# to-pcbway.net
KiCad netlist of a schematic drawn in EAGLE
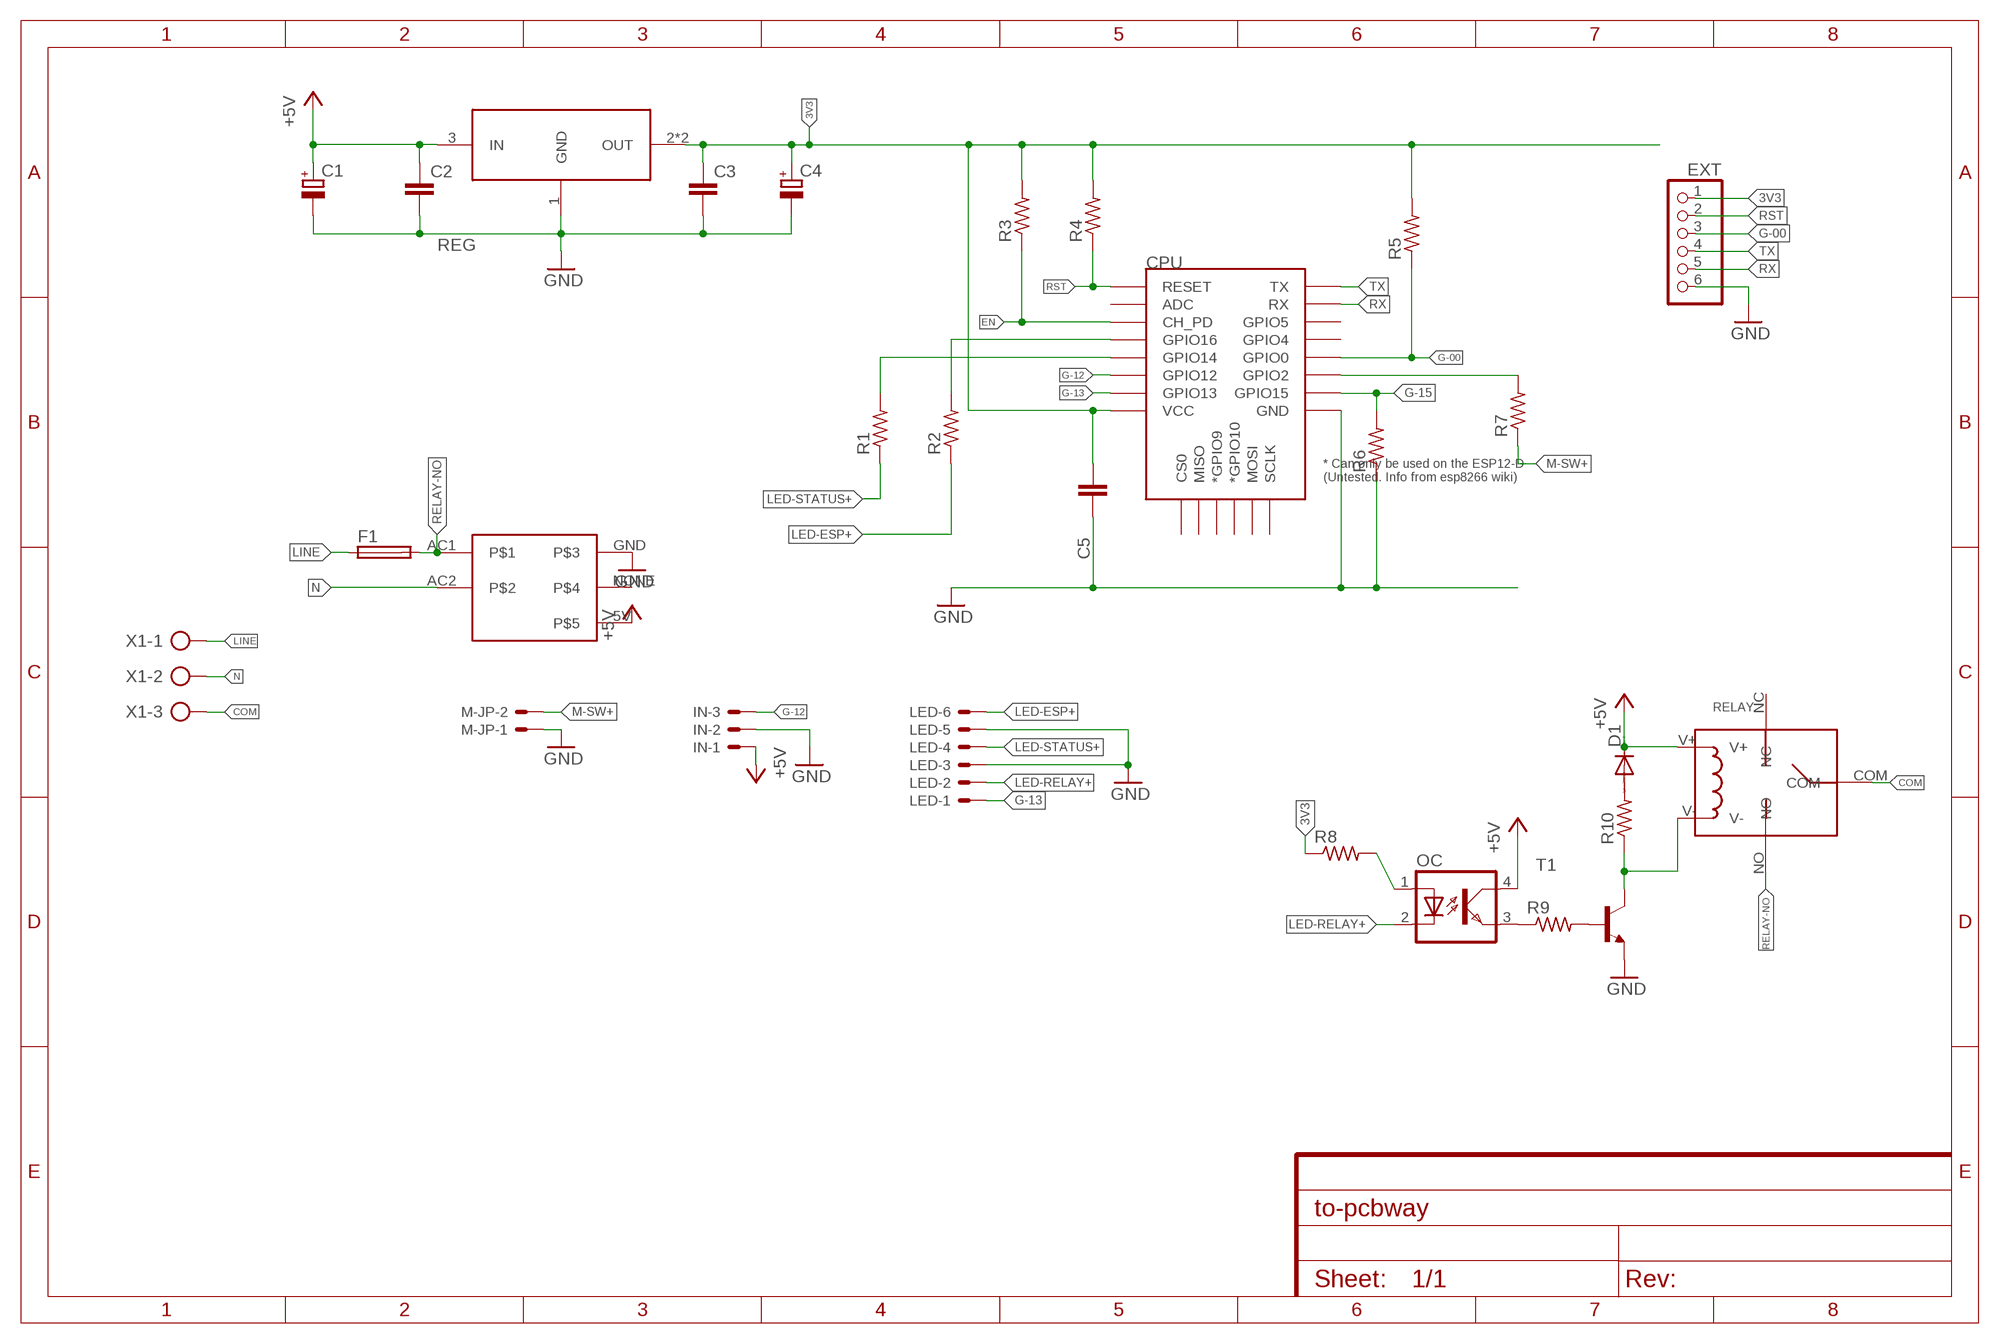
[diagram p0: schematic, sheet 1]

(export (version "E")
  (design (tool "Eeschema 10.0.6"))
  (components
    (comp (ref "C1")
      (value "CPOL-EUE2-5")
      (footprint "eagle-import:E2-5")
      (libsource (lib "eagle-import") (part "CPOL-EUE2-5"))
    )
    (comp (ref "C2")
      (value "C-EUC0603K")
      (footprint "eagle-import:C0603K")
      (libsource (lib "eagle-import") (part "C-EUC0603K"))
    )
    (comp (ref "C3")
      (value "C-EUC0603K")
      (footprint "eagle-import:C0603K")
      (libsource (lib "eagle-import") (part "C-EUC0603K"))
    )
    (comp (ref "C4")
      (value "CPOL-EUE2-5")
      (footprint "eagle-import:E2-5")
      (libsource (lib "eagle-import") (part "CPOL-EUE2-5"))
    )
    (comp (ref "C5")
      (value "C-EUC0805")
      (footprint "eagle-import:C0805")
      (libsource (lib "eagle-import") (part "C-EUC0805"))
    )
    (comp (ref "CPU")
      (value "ESP12ESMD")
      (footprint "eagle-import:ESP12E-SMD")
      (libsource (lib "eagle-import") (part "ESP12ESMD"))
    )
    (comp (ref "D1")
      (value "1N4148DO35-7")
      (footprint "eagle-import:DO35-7")
      (libsource (lib "eagle-import") (part "1N4148DO35-7"))
    )
    (comp (ref "EXT")
      (value "PINHD-1X6")
      (footprint "eagle-import:1X06")
      (libsource (lib "eagle-import") (part "PINHD-1X6"))
    )
    (comp (ref "F1")
      (value "FUSESH22,5")
      (footprint "eagle-import:SH22,5")
      (libsource (lib "eagle-import") (part "FUSESH22,5"))
    )
    (comp (ref "IN")
      (value "53048-03")
      (footprint "eagle-import:53048-03")
      (fields (field (name "MF") "WALDOM/MOLEX") (field (name "MPN") "53048-0310"))
      (libsource (lib "eagle-import") (part "53?-03048"))
    )
    (comp (ref "LED")
      (value "53048-06")
      (footprint "eagle-import:53048-06")
      (fields (field (name "MF") "WALDOM/MOLEX") (field (name "MPN") "53048-0610"))
      (libsource (lib "eagle-import") (part "53?-06048"))
    )
    (comp (ref "M-JP")
      (value "53048-02")
      (footprint "eagle-import:53048-02")
      (fields (field (name "MF") "MOLEX") (field (name "MPN") "53048-0210"))
      (libsource (lib "eagle-import") (part "53?-02048"))
    )
    (comp (ref "OC")
      (value "PC817")
      (footprint "eagle-import:DIL04")
      (fields (field (name "MPN") "PC817X4J000F"))
      (libsource (lib "eagle-import") (part "PC817"))
    )
    (comp (ref "R1")
      (value "R-US_R0603")
      (footprint "eagle-import:R0603")
      (libsource (lib "eagle-import") (part "R-US_R0603"))
    )
    (comp (ref "R2")
      (value "R-US_R0603")
      (footprint "eagle-import:R0603")
      (libsource (lib "eagle-import") (part "R-US_R0603"))
    )
    (comp (ref "R3")
      (value "R-US_R0603")
      (footprint "eagle-import:R0603")
      (libsource (lib "eagle-import") (part "R-US_R0603"))
    )
    (comp (ref "R4")
      (value "R-US_R0603")
      (footprint "eagle-import:R0603")
      (libsource (lib "eagle-import") (part "R-US_R0603"))
    )
    (comp (ref "R5")
      (value "R-US_R0603")
      (footprint "eagle-import:R0603")
      (libsource (lib "eagle-import") (part "R-US_R0603"))
    )
    (comp (ref "R6")
      (value "R-US_R0603")
      (footprint "eagle-import:R0603")
      (libsource (lib "eagle-import") (part "R-US_R0603"))
    )
    (comp (ref "R7")
      (value "R-US_R0603")
      (footprint "eagle-import:R0603")
      (libsource (lib "eagle-import") (part "R-US_R0603"))
    )
    (comp (ref "R8")
      (value "R-US_M0805")
      (footprint "eagle-import:M0805")
      (libsource (lib "eagle-import") (part "R-US_M0805"))
    )
    (comp (ref "R9")
      (value "R-US_M0805")
      (footprint "eagle-import:M0805")
      (libsource (lib "eagle-import") (part "R-US_M0805"))
    )
    (comp (ref "R10")
      (value "R-US_M0805")
      (footprint "eagle-import:M0805")
      (libsource (lib "eagle-import") (part "R-US_M0805"))
    )
    (comp (ref "REG")
      (value "AMS1117-3.3")
      (footprint "eagle-import:SOT-223")
      (libsource (lib "eagle-import") (part "AMS1117-3.3"))
    )
    (comp (ref "RELAY")
      (value "RELAY-SONGLE")
      (footprint "eagle-import:RELAY-SONGLE")
      (libsource (lib "eagle-import") (part "RELAY-SONGLE"))
    )
    (comp (ref "T1")
      (value "BC817-NPN-SOT23-BEC")
      (footprint "eagle-import:SOT23-BEC")
      (libsource (lib "eagle-import") (part "-NPN-SOT23-BECBC817"))
    )
    (comp (ref "U$4")
      (value "POWERSUPPLY-5V-700MA")
      (footprint "eagle-import:POWERSUPPLY-5V-700MA")
      (libsource (lib "eagle-import") (part "POWERSUPPLY-5V-700MA"))
    )
    (comp (ref "X1")
      (value "AK300/3")
      (footprint "eagle-import:AK300_3")
      (libsource (lib "eagle-import") (part "AK300/3"))
    )
  )
  (nets
    (net (code "1") (name "+5V") (class "Default")
      (node (ref "C1") (pin "+") (pinfunction "+_+") (pintype "passive"))
      (node (ref "C2") (pin "1") (pinfunction "1_1") (pintype "passive"))
      (node (ref "D1") (pin "C") (pinfunction "C_C") (pintype "passive"))
      (node (ref "IN") (pin "1") (pinfunction "S_1") (pintype "passive"))
      (node (ref "OC") (pin "4") (pinfunction "COL_4") (pintype "passive"))
      (node (ref "REG") (pin "3") (pinfunction "IN_3") (pintype "input"))
      (node (ref "RELAY") (pin "V+") (pinfunction "V+_V+") (pintype "bidirectional"))
      (node (ref "U$4") (pin "5V") (pinfunction "P$5_5V") (pintype "bidirectional"))
    )
    (net (code "2") (name "3V3") (class "Default")
      (node (ref "C3") (pin "1") (pinfunction "1_1") (pintype "passive"))
      (node (ref "C4") (pin "+") (pinfunction "+_+") (pintype "passive"))
      (node (ref "C5") (pin "1") (pinfunction "1_1") (pintype "passive"))
      (node (ref "CPU") (pin "VCC") (pinfunction "VCC_VCC") (pintype "bidirectional"))
      (node (ref "EXT") (pin "1") (pinfunction "1_1") (pintype "passive"))
      (node (ref "R3") (pin "2") (pinfunction "2_2") (pintype "passive"))
      (node (ref "R4") (pin "2") (pinfunction "2_2") (pintype "passive"))
      (node (ref "R5") (pin "2") (pinfunction "2_2") (pintype "passive"))
      (node (ref "R8") (pin "1") (pinfunction "1_1") (pintype "passive"))
      (node (ref "REG") (pin "2") (pinfunction "OUT_2") (pintype "output"))
      (node (ref "REG") (pin "4") (pinfunction "OUT_4") (pintype "output"))
    )
    (net (code "3") (name "COM") (class "Default")
      (node (ref "RELAY") (pin "COM") (pinfunction "COM_COM") (pintype "bidirectional"))
      (node (ref "X1") (pin "3") (pinfunction "KL_3") (pintype "passive"))
    )
    (net (code "4") (name "EN") (class "Default")
      (node (ref "CPU") (pin "CH_PD") (pinfunction "CH_PD_CH_PD") (pintype "bidirectional"))
      (node (ref "R3") (pin "1") (pinfunction "1_1") (pintype "passive"))
    )
    (net (code "5") (name "G-00") (class "Default")
      (node (ref "CPU") (pin "GPIO0") (pinfunction "GPIO0_GPIO0") (pintype "bidirectional"))
      (node (ref "EXT") (pin "3") (pinfunction "3_3") (pintype "passive"))
      (node (ref "R5") (pin "1") (pinfunction "1_1") (pintype "passive"))
    )
    (net (code "6") (name "G-12") (class "Default")
      (node (ref "CPU") (pin "GPIO12") (pinfunction "GPIO12_GPIO12") (pintype "bidirectional"))
      (node (ref "IN") (pin "3") (pinfunction "S_3") (pintype "passive"))
    )
    (net (code "7") (name "G-13") (class "Default")
      (node (ref "CPU") (pin "GPIO13") (pinfunction "GPIO13_GPIO13") (pintype "bidirectional"))
      (node (ref "LED") (pin "1") (pinfunction "S_1") (pintype "passive"))
    )
    (net (code "8") (name "G-15") (class "Default")
      (node (ref "CPU") (pin "GPIO15") (pinfunction "GPIO15_GPIO15") (pintype "bidirectional"))
      (node (ref "R6") (pin "2") (pinfunction "2_2") (pintype "passive"))
    )
    (net (code "9") (name "GND") (class "Default")
      (node (ref "C1") (pin "-") (pinfunction "-_-") (pintype "passive"))
      (node (ref "C2") (pin "2") (pinfunction "2_2") (pintype "passive"))
      (node (ref "C3") (pin "2") (pinfunction "2_2") (pintype "passive"))
      (node (ref "C4") (pin "-") (pinfunction "-_-") (pintype "passive"))
      (node (ref "C5") (pin "2") (pinfunction "2_2") (pintype "passive"))
      (node (ref "CPU") (pin "GND") (pinfunction "GND_GND") (pintype "bidirectional"))
      (node (ref "EXT") (pin "6") (pinfunction "6_6") (pintype "passive"))
      (node (ref "IN") (pin "2") (pinfunction "S_2") (pintype "passive"))
      (node (ref "LED") (pin "3") (pinfunction "S_3") (pintype "passive"))
      (node (ref "LED") (pin "5") (pinfunction "S_5") (pintype "passive"))
      (node (ref "M-JP") (pin "1") (pinfunction "S_1") (pintype "passive"))
      (node (ref "R6") (pin "1") (pinfunction "1_1") (pintype "passive"))
      (node (ref "REG") (pin "1") (pinfunction "GND_1") (pintype "passive"))
      (node (ref "T1") (pin "E") (pinfunction "E_E") (pintype "passive"))
      (node (ref "U$4") (pin "GND") (pinfunction "P$3_GND") (pintype "bidirectional"))
    )
    (net (code "10") (name "LED-ESP+") (class "Default")
      (node (ref "LED") (pin "6") (pinfunction "S_6") (pintype "passive"))
      (node (ref "R2") (pin "1") (pinfunction "1_1") (pintype "passive"))
    )
    (net (code "11") (name "LED-RELAY+") (class "Default")
      (node (ref "LED") (pin "2") (pinfunction "S_2") (pintype "passive"))
      (node (ref "OC") (pin "2") (pinfunction "C_2") (pintype "passive"))
    )
    (net (code "12") (name "LED-STATUS+") (class "Default")
      (node (ref "LED") (pin "4") (pinfunction "S_4") (pintype "passive"))
      (node (ref "R1") (pin "1") (pinfunction "1_1") (pintype "passive"))
    )
    (net (code "13") (name "LINE") (class "Default")
      (node (ref "F1") (pin "1") (pinfunction "1_1") (pintype "passive"))
      (node (ref "X1") (pin "1") (pinfunction "KL_1") (pintype "passive"))
    )
    (net (code "14") (name "M-SW+") (class "Default")
      (node (ref "M-JP") (pin "2") (pinfunction "S_2") (pintype "passive"))
      (node (ref "R7") (pin "1") (pinfunction "1_1") (pintype "passive"))
    )
    (net (code "15") (name "N") (class "Default")
      (node (ref "U$4") (pin "AC2") (pinfunction "P$2_AC2") (pintype "bidirectional"))
      (node (ref "X1") (pin "2") (pinfunction "KL_2") (pintype "passive"))
    )
    (net (code "16") (name "Net-(CPU-PadGPIO2)") (class "Default")
      (node (ref "CPU") (pin "GPIO2") (pinfunction "GPIO2_GPIO2") (pintype "bidirectional"))
      (node (ref "R7") (pin "2") (pinfunction "2_2") (pintype "passive"))
    )
    (net (code "17") (name "Net-(CPU-PadGPIO14)") (class "Default")
      (node (ref "CPU") (pin "GPIO14") (pinfunction "GPIO14_GPIO14") (pintype "bidirectional"))
      (node (ref "R1") (pin "2") (pinfunction "2_2") (pintype "passive"))
    )
    (net (code "18") (name "Net-(CPU-PadGPIO16)") (class "Default")
      (node (ref "CPU") (pin "GPIO16") (pinfunction "GPIO16_GPIO16") (pintype "bidirectional"))
      (node (ref "R2") (pin "2") (pinfunction "2_2") (pintype "passive"))
    )
    (net (code "19") (name "Net-(D1-PadA)") (class "Default")
      (node (ref "D1") (pin "A") (pinfunction "A_A") (pintype "passive"))
      (node (ref "R10") (pin "2") (pinfunction "2_2") (pintype "passive"))
    )
    (net (code "20") (name "Net-(OC-A)") (class "Default")
      (node (ref "OC") (pin "1") (pinfunction "A_1") (pintype "passive"))
      (node (ref "R8") (pin "2") (pinfunction "2_2") (pintype "passive"))
    )
    (net (code "21") (name "Net-(OC-EMIT)") (class "Default")
      (node (ref "OC") (pin "3") (pinfunction "EMIT_3") (pintype "passive"))
      (node (ref "R9") (pin "1") (pinfunction "1_1") (pintype "passive"))
    )
    (net (code "22") (name "Net-(R9-Pad2)") (class "Default")
      (node (ref "R9") (pin "2") (pinfunction "2_2") (pintype "passive"))
      (node (ref "T1") (pin "B") (pinfunction "B_B") (pintype "passive"))
    )
    (net (code "23") (name "Net-(R10-Pad1)") (class "Default")
      (node (ref "R10") (pin "1") (pinfunction "1_1") (pintype "passive"))
      (node (ref "RELAY") (pin "V-") (pinfunction "V-_V-") (pintype "bidirectional"))
      (node (ref "T1") (pin "C") (pinfunction "C_C") (pintype "passive"))
    )
    (net (code "24") (name "RELAY-NO") (class "Default")
      (node (ref "F1") (pin "2") (pinfunction "2_2") (pintype "passive"))
      (node (ref "RELAY") (pin "NO") (pinfunction "NO_NO") (pintype "bidirectional"))
      (node (ref "U$4") (pin "AC1") (pinfunction "P$1_AC1") (pintype "bidirectional"))
    )
    (net (code "25") (name "RST") (class "Default")
      (node (ref "CPU") (pin "RESET") (pinfunction "RESET_RESET") (pintype "bidirectional"))
      (node (ref "EXT") (pin "2") (pinfunction "2_2") (pintype "passive"))
      (node (ref "R4") (pin "1") (pinfunction "1_1") (pintype "passive"))
    )
    (net (code "26") (name "RX") (class "Default")
      (node (ref "CPU") (pin "RXD0") (pinfunction "RX_RXD0") (pintype "bidirectional"))
      (node (ref "EXT") (pin "5") (pinfunction "5_5") (pintype "passive"))
    )
    (net (code "27") (name "TX") (class "Default")
      (node (ref "CPU") (pin "TXD0") (pinfunction "TX_TXD0") (pintype "bidirectional"))
      (node (ref "EXT") (pin "4") (pinfunction "4_4") (pintype "passive"))
    )
    (net (code "28") (name "unconnected-(CPU-*GPIO9-PadGPIO9)") (class "Default")
      (node (ref "CPU") (pin "GPIO9") (pinfunction "*GPIO9_GPIO9") (pintype "bidirectional"))
    )
    (net (code "29") (name "unconnected-(CPU-*GPIO10-PadGPIO10)") (class "Default")
      (node (ref "CPU") (pin "GPIO10") (pinfunction "*GPIO10_GPIO10") (pintype "bidirectional"))
    )
    (net (code "30") (name "unconnected-(CPU-PadADC)") (class "Default")
      (node (ref "CPU") (pin "ADC") (pinfunction "ADC_ADC") (pintype "bidirectional"))
    )
    (net (code "31") (name "unconnected-(CPU-PadCS0)") (class "Default")
      (node (ref "CPU") (pin "CS0") (pinfunction "CS0_CS0") (pintype "bidirectional"))
    )
    (net (code "32") (name "unconnected-(CPU-PadGPIO4)") (class "Default")
      (node (ref "CPU") (pin "GPIO4") (pinfunction "GPIO4_GPIO4") (pintype "bidirectional"))
    )
    (net (code "33") (name "unconnected-(CPU-PadGPIO5)") (class "Default")
      (node (ref "CPU") (pin "GPIO5") (pinfunction "GPIO5_GPIO5") (pintype "bidirectional"))
    )
    (net (code "34") (name "unconnected-(CPU-PadMISO)") (class "Default")
      (node (ref "CPU") (pin "MISO") (pinfunction "MISO_MISO") (pintype "bidirectional"))
    )
    (net (code "35") (name "unconnected-(CPU-PadMOSI)") (class "Default")
      (node (ref "CPU") (pin "MOSI") (pinfunction "MOSI_MOSI") (pintype "bidirectional"))
    )
    (net (code "36") (name "unconnected-(CPU-PadSCLK)") (class "Default")
      (node (ref "CPU") (pin "SCLK") (pinfunction "SCLK_SCLK") (pintype "bidirectional"))
    )
    (net (code "37") (name "unconnected-(RELAY-PadNC)") (class "Default")
      (node (ref "RELAY") (pin "NC") (pinfunction "NC_NC") (pintype "bidirectional"))
    )
    (net (code "38") (name "unconnected-(U$4-P$4-PadNONE)") (class "Default")
      (node (ref "U$4") (pin "NONE") (pinfunction "P$4_NONE") (pintype "bidirectional"))
    )
  )
)
